# 200PinConnector.net
KiCad netlist of a schematic drawn in Altium Designer
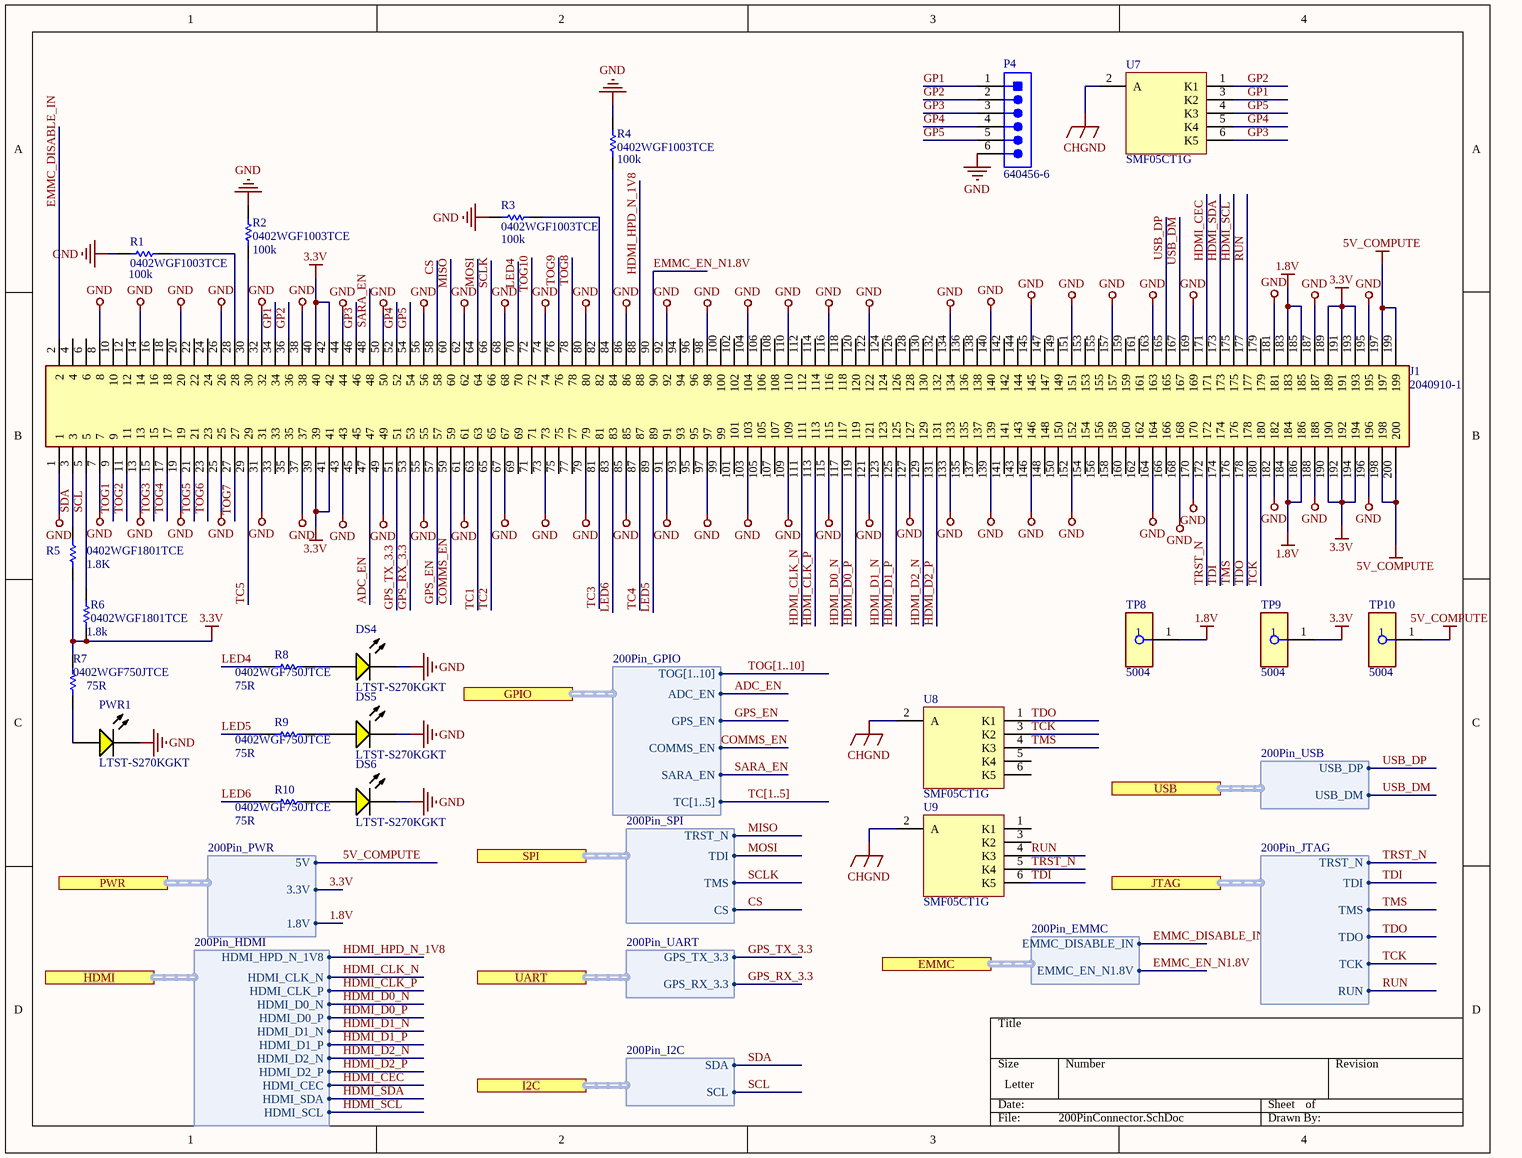
[diagram p0: 200PinConnector.SchDoc]

(export (version "E")
  (design (tool "Eeschema 10.0.6"))
  (components
    (comp (ref "DS4")
      (value "LTST-S270KGKT")
      (footprint "AVAG-HSMX-C190_V")
      (description "LED Uni-Color Yellow, 65 mW, 20 mA, -40 to 85 degC, 2-Pin SMD, RoHS, Tape and Reel")
      (fields (field (name "TOLERANCE") "1%"))
      (libsource (lib "Altium Content Vault") (part "LED-YELLOW-AK-2"))
    )
    (comp (ref "DS5")
      (value "LTST-S270KGKT")
      (footprint "AVAG-HSMX-C190_V")
      (description "LED Uni-Color Yellow, 65 mW, 20 mA, -40 to 85 degC, 2-Pin SMD, RoHS, Tape and Reel")
      (fields (field (name "TOLERANCE") "1%"))
      (libsource (lib "Altium Content Vault") (part "LED-YELLOW-AK-2"))
    )
    (comp (ref "DS6")
      (value "LTST-S270KGKT")
      (footprint "AVAG-HSMX-C190_V")
      (description "LED Uni-Color Yellow, 65 mW, 20 mA, -40 to 85 degC, 2-Pin SMD, RoHS, Tape and Reel")
      (fields (field (name "TOLERANCE") "1%"))
      (libsource (lib "Altium Content Vault") (part "LED-YELLOW-AK-2"))
    )
    (comp (ref "J1")
      (value "2040910-1")
      (footprint "20409101")
      (description "200 Pin Connector")
      (fields (field (name "MOUSER PART NUMBER") "571-2040910-1"))
      (libsource (lib "*") (part "2040910-1"))
    )
    (comp (ref "P4")
      (value "640456-6")
      (footprint "TECO-640456-6_V")
      (fields (field (name "MANUFACTURER") "TE Connectivity"))
      (libsource (lib "Altium Content Vault") (part "CN-1P-M-R6"))
    )
    (comp (ref "PWR1")
      (value "LTST-S270KGKT")
      (footprint "AVAG-HSMX-C190_V")
      (description "LED Uni-Color Yellow, 65 mW, 20 mA, -40 to 85 degC, 2-Pin SMD, RoHS, Tape and Reel")
      (fields (field (name "TOLERANCE") "1%"))
      (libsource (lib "Altium Content Vault") (part "LED-YELLOW-AK-2"))
    )
    (comp (ref "R1")
      (value "0402WGF1003TCE")
      (footprint "0402")
      (description "100k 0402")
      (fields (field (name "PUBLISHER") "Altium Limited"))
      (libsource (lib "Miscellaneous Devices") (part "Res1"))
    )
    (comp (ref "R2")
      (value "0402WGF1003TCE")
      (footprint "0402")
      (description "100k 0402")
      (fields (field (name "PUBLISHER") "Altium Limited"))
      (libsource (lib "Miscellaneous Devices") (part "Res1"))
    )
    (comp (ref "R3")
      (value "0402WGF1003TCE")
      (footprint "0402")
      (description "100k 0402")
      (fields (field (name "PUBLISHER") "Altium Limited"))
      (libsource (lib "Miscellaneous Devices") (part "Res1"))
    )
    (comp (ref "R4")
      (value "0402WGF1003TCE")
      (footprint "0402")
      (description "100k 0402")
      (fields (field (name "PUBLISHER") "Altium Limited"))
      (libsource (lib "Miscellaneous Devices") (part "Res1"))
    )
    (comp (ref "R5")
      (value "0402WGF1801TCE")
      (footprint "0402")
      (description "1.8k 0402")
      (fields (field (name "ALTIUM_VALUE") "1.8K") (field (name "PUBLISHER") "Altium Limited"))
      (libsource (lib "Miscellaneous Devices") (part "Res1"))
    )
    (comp (ref "R6")
      (value "0402WGF1801TCE")
      (footprint "0402")
      (description "1.8k 0402")
      (fields (field (name "PUBLISHER") "Altium Limited"))
      (libsource (lib "Miscellaneous Devices") (part "Res1"))
    )
    (comp (ref "R7")
      (value "0402WGF750JTCE")
      (footprint "RESC1005X40X25ML05T10")
      (description "75R 0402")
      (fields (field (name "PART NUMBER") "RC0402FR-07100RL") (field (name "MANUFACTURER") "Yageo / Phycomp"))
      (libsource (lib "Altium Content Vault") (part "RES"))
    )
    (comp (ref "R8")
      (value "0402WGF750JTCE")
      (footprint "RESC1005X40X25ML05T10")
      (description "75R 0402")
      (fields (field (name "PART NUMBER") "RC0402FR-07100RL") (field (name "MANUFACTURER") "Yageo / Phycomp"))
      (libsource (lib "Altium Content Vault") (part "RES"))
    )
    (comp (ref "R9")
      (value "0402WGF750JTCE")
      (footprint "RESC1005X40X25ML05T10")
      (description "75R 0402")
      (fields (field (name "PART NUMBER") "RC0402FR-07100RL") (field (name "MANUFACTURER") "Yageo / Phycomp"))
      (libsource (lib "Altium Content Vault") (part "RES"))
    )
    (comp (ref "R10")
      (value "0402WGF750JTCE")
      (footprint "RESC1005X40X25ML05T10")
      (description "75R 0402")
      (fields (field (name "PART NUMBER") "RC0402FR-07100RL") (field (name "MANUFACTURER") "Yageo / Phycomp"))
      (libsource (lib "Altium Content Vault") (part "RES"))
    )
    (comp (ref "TP8")
      (value "5004")
      (footprint "FP-5004-MFG")
      (description "PC TEST POINT MINIATURE YELLOW")
      (fields
        (field (name "MANUFACTURER") "Keystone")
        (field (name "OCTOPART") "https://octopart.com/5004-keystone-28591")
      )
      (libsource (lib "Altium Content Vault") (part "98815daf2f2c152b0c43f5ab9800df6"))
    )
    (comp (ref "TP9")
      (value "5004")
      (footprint "FP-5004-MFG")
      (description "PC TEST POINT MINIATURE YELLOW")
      (fields
        (field (name "MANUFACTURER") "Keystone")
        (field (name "OCTOPART") "https://octopart.com/5004-keystone-28591")
      )
      (libsource (lib "Altium Content Vault") (part "98815daf2f2c152b0c43f5ab9800df6"))
    )
    (comp (ref "TP10")
      (value "5004")
      (footprint "FP-5004-MFG")
      (description "PC TEST POINT MINIATURE YELLOW")
      (fields
        (field (name "MANUFACTURER") "Keystone")
        (field (name "OCTOPART") "https://octopart.com/5004-keystone-28591")
      )
      (libsource (lib "Altium Content Vault") (part "98815daf2f2c152b0c43f5ab9800df6"))
    )
    (comp (ref "U7")
      (value "SMF05CT1G")
      (footprint "ONSC-SC70-6-419B-02_W_V")
      (description "5-Line Transient Voltage Suppressor Array, 6-Pin SC70, Pb-Free, Tape and Reel")
      (fields (field (name "MANUFACTURER") "On Semiconductor"))
      (libsource (lib "Altium Content Vault") (part "ONSC-K1A2K3K4K5K6-6"))
    )
    (comp (ref "U8")
      (value "SMF05CT1G")
      (footprint "ONSC-SC70-6-419B-02_W_V")
      (description "5-Line Transient Voltage Suppressor Array, 6-Pin SC70, Pb-Free, Tape and Reel")
      (fields (field (name "MANUFACTURER") "On Semiconductor"))
      (libsource (lib "Altium Content Vault") (part "ONSC-K1A2K3K4K5K6-6"))
    )
    (comp (ref "U9")
      (value "SMF05CT1G")
      (footprint "ONSC-SC70-6-419B-02_W_V")
      (description "5-Line Transient Voltage Suppressor Array, 6-Pin SC70, Pb-Free, Tape and Reel")
      (fields (field (name "MANUFACTURER") "On Semiconductor"))
      (libsource (lib "Altium Content Vault") (part "ONSC-K1A2K3K4K5K6-6"))
    )
  )
  (nets
    (net (code "10") (name "/ADC_EN") (class "Default")
      (node (ref "J1") (pin "47") (pinfunction "47_47") (pintype "passive"))
    )
    (net (code "11") (name "/COMMS_EN") (class "Default")
      (node (ref "J1") (pin "59") (pinfunction "59_59") (pintype "passive"))
    )
    (net (code "12") (name "/CS") (class "Default")
      (node (ref "J1") (pin "58") (pinfunction "58_58") (pintype "passive"))
    )
    (net (code "13") (name "/EMMC_DISABLE_IN") (class "Default")
      (node (ref "J1") (pin "2") (pinfunction "2_2") (pintype "passive"))
    )
    (net (code "14") (name "/EMMC_EN_N1.8V") (class "Default")
      (node (ref "J1") (pin "90") (pinfunction "90_90") (pintype "passive"))
    )
    (net (code "15") (name "/GP1") (class "Default")
      (node (ref "J1") (pin "34") (pinfunction "34_34") (pintype "passive"))
      (node (ref "P4") (pin "1") (pinfunction "1_1") (pintype "passive"))
      (node (ref "U7") (pin "3") (pinfunction "K2_3") (pintype "passive"))
    )
    (net (code "16") (name "/GP2") (class "Default")
      (node (ref "J1") (pin "36") (pinfunction "36_36") (pintype "passive"))
      (node (ref "P4") (pin "2") (pinfunction "2_2") (pintype "passive"))
      (node (ref "U7") (pin "1") (pinfunction "K1_1") (pintype "passive"))
    )
    (net (code "17") (name "/GP3") (class "Default")
      (node (ref "J1") (pin "46") (pinfunction "46_46") (pintype "passive"))
      (node (ref "P4") (pin "3") (pinfunction "3_3") (pintype "passive"))
      (node (ref "U7") (pin "6") (pinfunction "K5_6") (pintype "passive"))
    )
    (net (code "18") (name "/GP4") (class "Default")
      (node (ref "J1") (pin "52") (pinfunction "52_52") (pintype "passive"))
      (node (ref "P4") (pin "4") (pinfunction "4_4") (pintype "passive"))
      (node (ref "U7") (pin "5") (pinfunction "K4_5") (pintype "passive"))
    )
    (net (code "19") (name "/GP5") (class "Default")
      (node (ref "J1") (pin "54") (pinfunction "54_54") (pintype "passive"))
      (node (ref "P4") (pin "5") (pinfunction "5_5") (pintype "passive"))
      (node (ref "U7") (pin "4") (pinfunction "K3_4") (pintype "passive"))
    )
    (net (code "20") (name "/GPS_EN") (class "Default")
      (node (ref "J1") (pin "57") (pinfunction "57_57") (pintype "passive"))
    )
    (net (code "21") (name "/GPS_RX_3.3") (class "Default")
      (node (ref "J1") (pin "53") (pinfunction "53_53") (pintype "passive"))
    )
    (net (code "22") (name "/GPS_TX_3.3") (class "Default")
      (node (ref "J1") (pin "51") (pinfunction "51_51") (pintype "passive"))
    )
    (net (code "23") (name "/HDMI_CEC") (class "Default")
      (node (ref "J1") (pin "171") (pinfunction "171_171") (pintype "passive"))
    )
    (net (code "24") (name "/HDMI_CLK_N") (class "Default")
      (node (ref "J1") (pin "111") (pinfunction "111_111") (pintype "passive"))
    )
    (net (code "25") (name "/HDMI_CLK_P") (class "Default")
      (node (ref "J1") (pin "113") (pinfunction "113_113") (pintype "passive"))
    )
    (net (code "26") (name "/HDMI_D0_N") (class "Default")
      (node (ref "J1") (pin "117") (pinfunction "117_117") (pintype "passive"))
    )
    (net (code "27") (name "/HDMI_D0_P") (class "Default")
      (node (ref "J1") (pin "119") (pinfunction "119_119") (pintype "passive"))
    )
    (net (code "28") (name "/HDMI_D1_N") (class "Default")
      (node (ref "J1") (pin "123") (pinfunction "123_123") (pintype "passive"))
    )
    (net (code "29") (name "/HDMI_D1_P") (class "Default")
      (node (ref "J1") (pin "125") (pinfunction "125_125") (pintype "passive"))
    )
    (net (code "30") (name "/HDMI_D2_N") (class "Default")
      (node (ref "J1") (pin "129") (pinfunction "129_129") (pintype "passive"))
    )
    (net (code "31") (name "/HDMI_D2_P") (class "Default")
      (node (ref "J1") (pin "131") (pinfunction "131_131") (pintype "passive"))
    )
    (net (code "32") (name "/HDMI_HPD_N_1V8") (class "Default")
      (node (ref "J1") (pin "88") (pinfunction "88_88") (pintype "passive"))
    )
    (net (code "33") (name "/HDMI_SCL") (class "Default")
      (node (ref "J1") (pin "175") (pinfunction "175_175") (pintype "passive"))
    )
    (net (code "34") (name "/HDMI_SDA") (class "Default")
      (node (ref "J1") (pin "173") (pinfunction "173_173") (pintype "passive"))
    )
    (net (code "35") (name "/LED4") (class "Default")
      (node (ref "J1") (pin "70") (pinfunction "70_70") (pintype "passive"))
      (node (ref "R8") (pin "2") (pinfunction "2_2") (pintype "passive"))
    )
    (net (code "36") (name "/LED5") (class "Default")
      (node (ref "J1") (pin "89") (pinfunction "89_89") (pintype "passive"))
      (node (ref "R9") (pin "2") (pinfunction "2_2") (pintype "passive"))
    )
    (net (code "37") (name "/LED6") (class "Default")
      (node (ref "J1") (pin "83") (pinfunction "83_83") (pintype "passive"))
      (node (ref "R10") (pin "2") (pinfunction "2_2") (pintype "passive"))
    )
    (net (code "38") (name "/MISO") (class "Default")
      (node (ref "J1") (pin "60") (pinfunction "60_60") (pintype "passive"))
    )
    (net (code "39") (name "/MOSI") (class "Default")
      (node (ref "J1") (pin "64") (pinfunction "64_64") (pintype "passive"))
    )
    (net (code "40") (name "/RUN") (class "Default")
      (node (ref "J1") (pin "177") (pinfunction "177_177") (pintype "passive"))
      (node (ref "U9") (pin "4") (pinfunction "K3_4") (pintype "passive"))
    )
    (net (code "41") (name "/SARA_EN") (class "Default")
      (node (ref "J1") (pin "48") (pinfunction "48_48") (pintype "passive"))
    )
    (net (code "42") (name "/SCL") (class "Default")
      (node (ref "J1") (pin "5") (pinfunction "5_5") (pintype "passive"))
      (node (ref "R6") (pin "2") (pinfunction "2_2") (pintype "passive"))
    )
    (net (code "43") (name "/SCLK") (class "Default")
      (node (ref "J1") (pin "66") (pinfunction "66_66") (pintype "passive"))
    )
    (net (code "44") (name "/SDA") (class "Default")
      (node (ref "J1") (pin "3") (pinfunction "3_3") (pintype "passive"))
      (node (ref "R5") (pin "2") (pinfunction "2_2") (pintype "passive"))
    )
    (net (code "45") (name "/TC1") (class "Default")
      (node (ref "J1") (pin "63") (pinfunction "63_63") (pintype "passive"))
    )
    (net (code "46") (name "/TC2") (class "Default")
      (node (ref "J1") (pin "65") (pinfunction "65_65") (pintype "passive"))
    )
    (net (code "47") (name "/TC3") (class "Default")
      (node (ref "J1") (pin "81") (pinfunction "81_81") (pintype "passive"))
    )
    (net (code "48") (name "/TC4") (class "Default")
      (node (ref "J1") (pin "87") (pinfunction "87_87") (pintype "passive"))
    )
    (net (code "49") (name "/TC5") (class "Default")
      (node (ref "J1") (pin "29") (pinfunction "29_29") (pintype "passive"))
    )
    (net (code "50") (name "/TCK") (class "Default")
      (node (ref "J1") (pin "180") (pinfunction "180_180") (pintype "passive"))
      (node (ref "U8") (pin "3") (pinfunction "K2_3") (pintype "passive"))
    )
    (net (code "52") (name "/TDI") (class "Default")
      (node (ref "J1") (pin "174") (pinfunction "174_174") (pintype "passive"))
      (node (ref "U9") (pin "6") (pinfunction "K5_6") (pintype "passive"))
    )
    (net (code "53") (name "/TDO") (class "Default")
      (node (ref "J1") (pin "178") (pinfunction "178_178") (pintype "passive"))
      (node (ref "U8") (pin "1") (pinfunction "K1_1") (pintype "passive"))
    )
    (net (code "54") (name "/TMS") (class "Default")
      (node (ref "J1") (pin "176") (pinfunction "176_176") (pintype "passive"))
      (node (ref "U8") (pin "4") (pinfunction "K3_4") (pintype "passive"))
    )
    (net (code "55") (name "/TOG1") (class "Default")
      (node (ref "J1") (pin "9") (pinfunction "9_9") (pintype "passive"))
    )
    (net (code "56") (name "/TOG2") (class "Default")
      (node (ref "J1") (pin "11") (pinfunction "11_11") (pintype "passive"))
    )
    (net (code "57") (name "/TOG3") (class "Default")
      (node (ref "J1") (pin "15") (pinfunction "15_15") (pintype "passive"))
    )
    (net (code "58") (name "/TOG4") (class "Default")
      (node (ref "J1") (pin "17") (pinfunction "17_17") (pintype "passive"))
    )
    (net (code "59") (name "/TOG5") (class "Default")
      (node (ref "J1") (pin "21") (pinfunction "21_21") (pintype "passive"))
    )
    (net (code "60") (name "/TOG6") (class "Default")
      (node (ref "J1") (pin "23") (pinfunction "23_23") (pintype "passive"))
    )
    (net (code "61") (name "/TOG7") (class "Default")
      (node (ref "J1") (pin "27") (pinfunction "27_27") (pintype "passive"))
    )
    (net (code "62") (name "/TOG8") (class "Default")
      (node (ref "J1") (pin "78") (pinfunction "78_78") (pintype "passive"))
    )
    (net (code "63") (name "/TOG9") (class "Default")
      (node (ref "J1") (pin "76") (pinfunction "76_76") (pintype "passive"))
    )
    (net (code "64") (name "/TOG10") (class "Default")
      (node (ref "J1") (pin "72") (pinfunction "72_72") (pintype "passive"))
    )
    (net (code "66") (name "/TRST_N") (class "Default")
      (node (ref "J1") (pin "172") (pinfunction "172_172") (pintype "passive"))
      (node (ref "U9") (pin "5") (pinfunction "K4_5") (pintype "passive"))
    )
    (net (code "67") (name "/USB_DM") (class "Default")
      (node (ref "J1") (pin "167") (pinfunction "167_167") (pintype "passive"))
    )
    (net (code "68") (name "/USB_DP") (class "Default")
      (node (ref "J1") (pin "165") (pinfunction "165_165") (pintype "passive"))
    )
    (net (code "78") (name "1.8V") (class "Default")
      (node (ref "J1") (pin "183") (pinfunction "183_183") (pintype "passive"))
      (node (ref "J1") (pin "184") (pinfunction "184_184") (pintype "passive"))
      (node (ref "J1") (pin "185") (pinfunction "185_185") (pintype "passive"))
      (node (ref "J1") (pin "186") (pinfunction "186_186") (pintype "passive"))
      (node (ref "TP8") (pin "1") (pinfunction "1_1") (pintype "passive"))
    )
    (net (code "79") (name "3.3V") (class "Default")
      (node (ref "J1") (pin "189") (pinfunction "189_189") (pintype "passive"))
      (node (ref "J1") (pin "190") (pinfunction "190_190") (pintype "passive"))
      (node (ref "J1") (pin "191") (pinfunction "191_191") (pintype "passive"))
      (node (ref "J1") (pin "192") (pinfunction "192_192") (pintype "passive"))
      (node (ref "J1") (pin "193") (pinfunction "193_193") (pintype "passive"))
      (node (ref "J1") (pin "194") (pinfunction "194_194") (pintype "passive"))
      (node (ref "J1") (pin "39") (pinfunction "39_39") (pintype "passive"))
      (node (ref "J1") (pin "40") (pinfunction "40_40") (pintype "passive"))
      (node (ref "J1") (pin "41") (pinfunction "41_41") (pintype "passive"))
      (node (ref "J1") (pin "42") (pinfunction "42_42") (pintype "passive"))
      (node (ref "R5") (pin "1") (pinfunction "1_1") (pintype "passive"))
      (node (ref "R6") (pin "1") (pinfunction "1_1") (pintype "passive"))
      (node (ref "R7") (pin "1") (pinfunction "1_1") (pintype "passive"))
      (node (ref "TP9") (pin "1") (pinfunction "1_1") (pintype "passive"))
    )
    (net (code "80") (name "5V_COMPUTE") (class "Default")
      (node (ref "J1") (pin "197") (pinfunction "197_197") (pintype "passive"))
      (node (ref "J1") (pin "198") (pinfunction "198_198") (pintype "passive"))
      (node (ref "J1") (pin "199") (pinfunction "199_199") (pintype "passive"))
      (node (ref "J1") (pin "200") (pinfunction "200_200") (pintype "passive"))
      (node (ref "TP10") (pin "1") (pinfunction "1_1") (pintype "passive"))
    )
    (net (code "81") (name "CHGND") (class "Default")
      (node (ref "U7") (pin "2") (pinfunction "A_2") (pintype "passive"))
      (node (ref "U8") (pin "2") (pinfunction "A_2") (pintype "passive"))
      (node (ref "U9") (pin "2") (pinfunction "A_2") (pintype "passive"))
    )
    (net (code "82") (name "GND") (class "Default")
      (node (ref "DS4") (pin "2") (pinfunction "K_2") (pintype "passive"))
      (node (ref "DS5") (pin "2") (pinfunction "K_2") (pintype "passive"))
      (node (ref "DS6") (pin "2") (pinfunction "K_2") (pintype "passive"))
      (node (ref "J1") (pin "1") (pinfunction "1_1") (pintype "passive"))
      (node (ref "J1") (pin "103") (pinfunction "103_103") (pintype "passive"))
      (node (ref "J1") (pin "104") (pinfunction "104_104") (pintype "passive"))
      (node (ref "J1") (pin "109") (pinfunction "109_109") (pintype "passive"))
      (node (ref "J1") (pin "110") (pinfunction "110_110") (pintype "passive"))
      (node (ref "J1") (pin "115") (pinfunction "115_115") (pintype "passive"))
      (node (ref "J1") (pin "116") (pinfunction "116_116") (pintype "passive"))
      (node (ref "J1") (pin "121") (pinfunction "121_121") (pintype "passive"))
      (node (ref "J1") (pin "122") (pinfunction "122_122") (pintype "passive"))
      (node (ref "J1") (pin "127") (pinfunction "127_127") (pintype "passive"))
      (node (ref "J1") (pin "13") (pinfunction "13_13") (pintype "passive"))
      (node (ref "J1") (pin "133") (pinfunction "133_133") (pintype "passive"))
      (node (ref "J1") (pin "134") (pinfunction "134_134") (pintype "passive"))
      (node (ref "J1") (pin "139") (pinfunction "139_139") (pintype "passive"))
      (node (ref "J1") (pin "14") (pinfunction "14_14") (pintype "passive"))
      (node (ref "J1") (pin "140") (pinfunction "140_140") (pintype "passive"))
      (node (ref "J1") (pin "145") (pinfunction "145_145") (pintype "passive"))
      (node (ref "J1") (pin "146") (pinfunction "146_146") (pintype "passive"))
      (node (ref "J1") (pin "151") (pinfunction "151_151") (pintype "passive"))
      (node (ref "J1") (pin "152") (pinfunction "152_152") (pintype "passive"))
      (node (ref "J1") (pin "157") (pinfunction "157_157") (pintype "passive"))
      (node (ref "J1") (pin "163") (pinfunction "163_163") (pintype "passive"))
      (node (ref "J1") (pin "164") (pinfunction "164_164") (pintype "passive"))
      (node (ref "J1") (pin "168") (pinfunction "168_168") (pintype "passive"))
      (node (ref "J1") (pin "169") (pinfunction "169_169") (pintype "passive"))
      (node (ref "J1") (pin "170") (pinfunction "170_170") (pintype "passive"))
      (node (ref "J1") (pin "181") (pinfunction "181_181") (pintype "passive"))
      (node (ref "J1") (pin "182") (pinfunction "182_182") (pintype "passive"))
      (node (ref "J1") (pin "187") (pinfunction "187_187") (pintype "passive"))
      (node (ref "J1") (pin "188") (pinfunction "188_188") (pintype "passive"))
      (node (ref "J1") (pin "19") (pinfunction "19_19") (pintype "passive"))
      (node (ref "J1") (pin "195") (pinfunction "195_195") (pintype "passive"))
      (node (ref "J1") (pin "196") (pinfunction "196_196") (pintype "passive"))
      (node (ref "J1") (pin "20") (pinfunction "20_20") (pintype "passive"))
      (node (ref "J1") (pin "25") (pinfunction "25_25") (pintype "passive"))
      (node (ref "J1") (pin "26") (pinfunction "26_26") (pintype "passive"))
      (node (ref "J1") (pin "31") (pinfunction "31_31") (pintype "passive"))
      (node (ref "J1") (pin "32") (pinfunction "32_32") (pintype "passive"))
      (node (ref "J1") (pin "37") (pinfunction "37_37") (pintype "passive"))
      (node (ref "J1") (pin "38") (pinfunction "38_38") (pintype "passive"))
      (node (ref "J1") (pin "43") (pinfunction "43_43") (pintype "passive"))
      (node (ref "J1") (pin "44") (pinfunction "44_44") (pintype "passive"))
      (node (ref "J1") (pin "49") (pinfunction "49_49") (pintype "passive"))
      (node (ref "J1") (pin "50") (pinfunction "50_50") (pintype "passive"))
      (node (ref "J1") (pin "55") (pinfunction "55_55") (pintype "passive"))
      (node (ref "J1") (pin "56") (pinfunction "56_56") (pintype "passive"))
      (node (ref "J1") (pin "61") (pinfunction "61_61") (pintype "passive"))
      (node (ref "J1") (pin "62") (pinfunction "62_62") (pintype "passive"))
      (node (ref "J1") (pin "67") (pinfunction "67_67") (pintype "passive"))
      (node (ref "J1") (pin "68") (pinfunction "68_68") (pintype "passive"))
      (node (ref "J1") (pin "7") (pinfunction "7_7") (pintype "passive"))
      (node (ref "J1") (pin "73") (pinfunction "73_73") (pintype "passive"))
      (node (ref "J1") (pin "74") (pinfunction "74_74") (pintype "passive"))
      (node (ref "J1") (pin "79") (pinfunction "79_79") (pintype "passive"))
      (node (ref "J1") (pin "8") (pinfunction "8_8") (pintype "passive"))
      (node (ref "J1") (pin "80") (pinfunction "80_80") (pintype "passive"))
      (node (ref "J1") (pin "85") (pinfunction "85_85") (pintype "passive"))
      (node (ref "J1") (pin "86") (pinfunction "86_86") (pintype "passive"))
      (node (ref "J1") (pin "91") (pinfunction "91_91") (pintype "passive"))
      (node (ref "J1") (pin "92") (pinfunction "92_92") (pintype "passive"))
      (node (ref "J1") (pin "97") (pinfunction "97_97") (pintype "passive"))
      (node (ref "J1") (pin "98") (pinfunction "98_98") (pintype "passive"))
      (node (ref "P4") (pin "6") (pinfunction "6_6") (pintype "passive"))
      (node (ref "PWR1") (pin "2") (pinfunction "K_2") (pintype "passive"))
      (node (ref "R1") (pin "2") (pinfunction "2_2") (pintype "passive"))
      (node (ref "R2") (pin "2") (pinfunction "2_2") (pintype "passive"))
      (node (ref "R3") (pin "2") (pinfunction "2_2") (pintype "passive"))
      (node (ref "R4") (pin "2") (pinfunction "2_2") (pintype "passive"))
    )
    (net (code "83") (name "Net-(DS4-A)") (class "Default")
      (node (ref "DS4") (pin "1") (pinfunction "A_1") (pintype "passive"))
      (node (ref "R8") (pin "1") (pinfunction "1_1") (pintype "passive"))
    )
    (net (code "84") (name "Net-(DS5-A)") (class "Default")
      (node (ref "DS5") (pin "1") (pinfunction "A_1") (pintype "passive"))
      (node (ref "R9") (pin "1") (pinfunction "1_1") (pintype "passive"))
    )
    (net (code "85") (name "Net-(DS6-A)") (class "Default")
      (node (ref "DS6") (pin "1") (pinfunction "A_1") (pintype "passive"))
      (node (ref "R10") (pin "1") (pinfunction "1_1") (pintype "passive"))
    )
    (net (code "86") (name "Net-(J1-Pad28)") (class "Default")
      (node (ref "J1") (pin "28") (pinfunction "28_28") (pintype "passive"))
      (node (ref "R1") (pin "1") (pinfunction "1_1") (pintype "passive"))
    )
    (net (code "87") (name "Net-(J1-Pad30)") (class "Default")
      (node (ref "J1") (pin "30") (pinfunction "30_30") (pintype "passive"))
      (node (ref "R2") (pin "1") (pinfunction "1_1") (pintype "passive"))
    )
    (net (code "88") (name "Net-(J1-Pad82)") (class "Default")
      (node (ref "J1") (pin "82") (pinfunction "82_82") (pintype "passive"))
      (node (ref "R3") (pin "1") (pinfunction "1_1") (pintype "passive"))
    )
    (net (code "89") (name "Net-(J1-Pad84)") (class "Default")
      (node (ref "J1") (pin "84") (pinfunction "84_84") (pintype "passive"))
      (node (ref "R4") (pin "1") (pinfunction "1_1") (pintype "passive"))
    )
    (net (code "90") (name "Net-(PWR1-A)") (class "Default")
      (node (ref "PWR1") (pin "1") (pinfunction "A_1") (pintype "passive"))
      (node (ref "R7") (pin "2") (pinfunction "2_2") (pintype "passive"))
    )
    (net (code "91") (name "unconnected-(J1-Pad4)") (class "Default")
      (node (ref "J1") (pin "4") (pinfunction "4_4") (pintype "passive"))
    )
    (net (code "92") (name "unconnected-(J1-Pad6)") (class "Default")
      (node (ref "J1") (pin "6") (pinfunction "6_6") (pintype "passive"))
    )
    (net (code "93") (name "unconnected-(J1-Pad10)") (class "Default")
      (node (ref "J1") (pin "10") (pinfunction "10_10") (pintype "passive"))
    )
    (net (code "94") (name "unconnected-(J1-Pad12)") (class "Default")
      (node (ref "J1") (pin "12") (pinfunction "12_12") (pintype "passive"))
    )
    (net (code "95") (name "unconnected-(J1-Pad16)") (class "Default")
      (node (ref "J1") (pin "16") (pinfunction "16_16") (pintype "passive"))
    )
    (net (code "96") (name "unconnected-(J1-Pad18)") (class "Default")
      (node (ref "J1") (pin "18") (pinfunction "18_18") (pintype "passive"))
    )
    (net (code "97") (name "unconnected-(J1-Pad22)") (class "Default")
      (node (ref "J1") (pin "22") (pinfunction "22_22") (pintype "passive"))
    )
    (net (code "98") (name "unconnected-(J1-Pad24)") (class "Default")
      (node (ref "J1") (pin "24") (pinfunction "24_24") (pintype "passive"))
    )
    (net (code "99") (name "unconnected-(J1-Pad33)") (class "Default")
      (node (ref "J1") (pin "33") (pinfunction "33_33") (pintype "passive"))
    )
    (net (code "100") (name "unconnected-(J1-Pad35)") (class "Default")
      (node (ref "J1") (pin "35") (pinfunction "35_35") (pintype "passive"))
    )
    (net (code "101") (name "unconnected-(J1-Pad45)") (class "Default")
      (node (ref "J1") (pin "45") (pinfunction "45_45") (pintype "passive"))
    )
    (net (code "102") (name "unconnected-(J1-Pad69)") (class "Default")
      (node (ref "J1") (pin "69") (pinfunction "69_69") (pintype "passive"))
    )
    (net (code "103") (name "unconnected-(J1-Pad71)") (class "Default")
      (node (ref "J1") (pin "71") (pinfunction "71_71") (pintype "passive"))
    )
    (net (code "104") (name "unconnected-(J1-Pad75)") (class "Default")
      (node (ref "J1") (pin "75") (pinfunction "75_75") (pintype "passive"))
    )
    (net (code "105") (name "unconnected-(J1-Pad77)") (class "Default")
      (node (ref "J1") (pin "77") (pinfunction "77_77") (pintype "passive"))
    )
    (net (code "106") (name "unconnected-(J1-Pad93)") (class "Default")
      (node (ref "J1") (pin "93") (pinfunction "93_93") (pintype "passive"))
    )
    (net (code "107") (name "unconnected-(J1-Pad94)") (class "Default")
      (node (ref "J1") (pin "94") (pinfunction "94_94") (pintype "passive"))
    )
    (net (code "108") (name "unconnected-(J1-Pad95)") (class "Default")
      (node (ref "J1") (pin "95") (pinfunction "95_95") (pintype "passive"))
    )
    (net (code "109") (name "unconnected-(J1-Pad96)") (class "Default")
      (node (ref "J1") (pin "96") (pinfunction "96_96") (pintype "passive"))
    )
    (net (code "110") (name "unconnected-(J1-Pad99)") (class "Default")
      (node (ref "J1") (pin "99") (pinfunction "99_99") (pintype "passive"))
    )
    (net (code "111") (name "unconnected-(J1-Pad100)") (class "Default")
      (node (ref "J1") (pin "100") (pinfunction "100_100") (pintype "passive"))
    )
    (net (code "112") (name "unconnected-(J1-Pad101)") (class "Default")
      (node (ref "J1") (pin "101") (pinfunction "101_101") (pintype "passive"))
    )
    (net (code "113") (name "unconnected-(J1-Pad102)") (class "Default")
      (node (ref "J1") (pin "102") (pinfunction "102_102") (pintype "passive"))
    )
    (net (code "114") (name "unconnected-(J1-Pad105)") (class "Default")
      (node (ref "J1") (pin "105") (pinfunction "105_105") (pintype "passive"))
    )
    (net (code "115") (name "unconnected-(J1-Pad106)") (class "Default")
      (node (ref "J1") (pin "106") (pinfunction "106_106") (pintype "passive"))
    )
    (net (code "116") (name "unconnected-(J1-Pad107)") (class "Default")
      (node (ref "J1") (pin "107") (pinfunction "107_107") (pintype "passive"))
    )
    (net (code "117") (name "unconnected-(J1-Pad108)") (class "Default")
      (node (ref "J1") (pin "108") (pinfunction "108_108") (pintype "passive"))
    )
    (net (code "118") (name "unconnected-(J1-Pad112)") (class "Default")
      (node (ref "J1") (pin "112") (pinfunction "112_112") (pintype "passive"))
    )
    (net (code "119") (name "unconnected-(J1-Pad114)") (class "Default")
      (node (ref "J1") (pin "114") (pinfunction "114_114") (pintype "passive"))
    )
    (net (code "120") (name "unconnected-(J1-Pad118)") (class "Default")
      (node (ref "J1") (pin "118") (pinfunction "118_118") (pintype "passive"))
    )
    (net (code "121") (name "unconnected-(J1-Pad120)") (class "Default")
      (node (ref "J1") (pin "120") (pinfunction "120_120") (pintype "passive"))
    )
    (net (code "122") (name "unconnected-(J1-Pad124)") (class "Default")
      (node (ref "J1") (pin "124") (pinfunction "124_124") (pintype "passive"))
    )
    (net (code "123") (name "unconnected-(J1-Pad126)") (class "Default")
      (node (ref "J1") (pin "126") (pinfunction "126_126") (pintype "passive"))
    )
    (net (code "124") (name "unconnected-(J1-Pad128)") (class "Default")
      (node (ref "J1") (pin "128") (pinfunction "128_128") (pintype "passive"))
    )
    (net (code "125") (name "unconnected-(J1-Pad130)") (class "Default")
      (node (ref "J1") (pin "130") (pinfunction "130_130") (pintype "passive"))
    )
    (net (code "126") (name "unconnected-(J1-Pad132)") (class "Default")
      (node (ref "J1") (pin "132") (pinfunction "132_132") (pintype "passive"))
    )
    (net (code "127") (name "unconnected-(J1-Pad135)") (class "Default")
      (node (ref "J1") (pin "135") (pinfunction "135_135") (pintype "passive"))
    )
    (net (code "128") (name "unconnected-(J1-Pad136)") (class "Default")
      (node (ref "J1") (pin "136") (pinfunction "136_136") (pintype "passive"))
    )
    (net (code "129") (name "unconnected-(J1-Pad137)") (class "Default")
      (node (ref "J1") (pin "137") (pinfunction "137_137") (pintype "passive"))
    )
    (net (code "130") (name "unconnected-(J1-Pad138)") (class "Default")
      (node (ref "J1") (pin "138") (pinfunction "138_138") (pintype "passive"))
    )
    (net (code "131") (name "unconnected-(J1-Pad141)") (class "Default")
      (node (ref "J1") (pin "141") (pinfunction "141_141") (pintype "passive"))
    )
    (net (code "132") (name "unconnected-(J1-Pad142)") (class "Default")
      (node (ref "J1") (pin "142") (pinfunction "142_142") (pintype "passive"))
    )
    (net (code "133") (name "unconnected-(J1-Pad143)") (class "Default")
      (node (ref "J1") (pin "143") (pinfunction "143_143") (pintype "passive"))
    )
    (net (code "134") (name "unconnected-(J1-Pad144)") (class "Default")
      (node (ref "J1") (pin "144") (pinfunction "144_144") (pintype "passive"))
    )
    (net (code "135") (name "unconnected-(J1-Pad147)") (class "Default")
      (node (ref "J1") (pin "147") (pinfunction "147_147") (pintype "passive"))
    )
    (net (code "136") (name "unconnected-(J1-Pad148)") (class "Default")
      (node (ref "J1") (pin "148") (pinfunction "148_148") (pintype "passive"))
    )
    (net (code "137") (name "unconnected-(J1-Pad149)") (class "Default")
      (node (ref "J1") (pin "149") (pinfunction "149_149") (pintype "passive"))
    )
    (net (code "138") (name "unconnected-(J1-Pad150)") (class "Default")
      (node (ref "J1") (pin "150") (pinfunction "150_150") (pintype "passive"))
    )
    (net (code "139") (name "unconnected-(J1-Pad153)") (class "Default")
      (node (ref "J1") (pin "153") (pinfunction "153_153") (pintype "passive"))
    )
    (net (code "140") (name "unconnected-(J1-Pad154)") (class "Default")
      (node (ref "J1") (pin "154") (pinfunction "154_154") (pintype "passive"))
    )
    (net (code "141") (name "unconnected-(J1-Pad155)") (class "Default")
      (node (ref "J1") (pin "155") (pinfunction "155_155") (pintype "passive"))
    )
    (net (code "142") (name "unconnected-(J1-Pad156)") (class "Default")
      (node (ref "J1") (pin "156") (pinfunction "156_156") (pintype "passive"))
    )
    (net (code "143") (name "unconnected-(J1-Pad158)") (class "Default")
      (node (ref "J1") (pin "158") (pinfunction "158_158") (pintype "passive"))
    )
    (net (code "144") (name "unconnected-(J1-Pad159)") (class "Default")
      (node (ref "J1") (pin "159") (pinfunction "159_159") (pintype "passive"))
    )
    (net (code "145") (name "unconnected-(J1-Pad160)") (class "Default")
      (node (ref "J1") (pin "160") (pinfunction "160_160") (pintype "passive"))
    )
    (net (code "146") (name "unconnected-(J1-Pad161)") (class "Default")
      (node (ref "J1") (pin "161") (pinfunction "161_161") (pintype "passive"))
    )
    (net (code "147") (name "unconnected-(J1-Pad162)") (class "Default")
      (node (ref "J1") (pin "162") (pinfunction "162_162") (pintype "passive"))
    )
    (net (code "148") (name "unconnected-(J1-Pad166)") (class "Default")
      (node (ref "J1") (pin "166") (pinfunction "166_166") (pintype "passive"))
    )
    (net (code "149") (name "unconnected-(J1-Pad179)") (class "Default")
      (node (ref "J1") (pin "179") (pinfunction "179_179") (pintype "passive"))
    )
    (net (code "150") (name "unconnected-(U8-K4-Pad5)") (class "Default")
      (node (ref "U8") (pin "5") (pinfunction "K4_5") (pintype "passive"))
    )
    (net (code "151") (name "unconnected-(U8-K5-Pad6)") (class "Default")
      (node (ref "U8") (pin "6") (pinfunction "K5_6") (pintype "passive"))
    )
    (net (code "152") (name "unconnected-(U9-K1-Pad1)") (class "Default")
      (node (ref "U9") (pin "1") (pinfunction "K1_1") (pintype "passive"))
    )
    (net (code "153") (name "unconnected-(U9-K2-Pad3)") (class "Default")
      (node (ref "U9") (pin "3") (pinfunction "K2_3") (pintype "passive"))
    )
  )
)
